# LB_BIT_i2_TOGGLESWITCH-v03_rev2.net
KiCad netlist of a schematic drawn in EAGLE
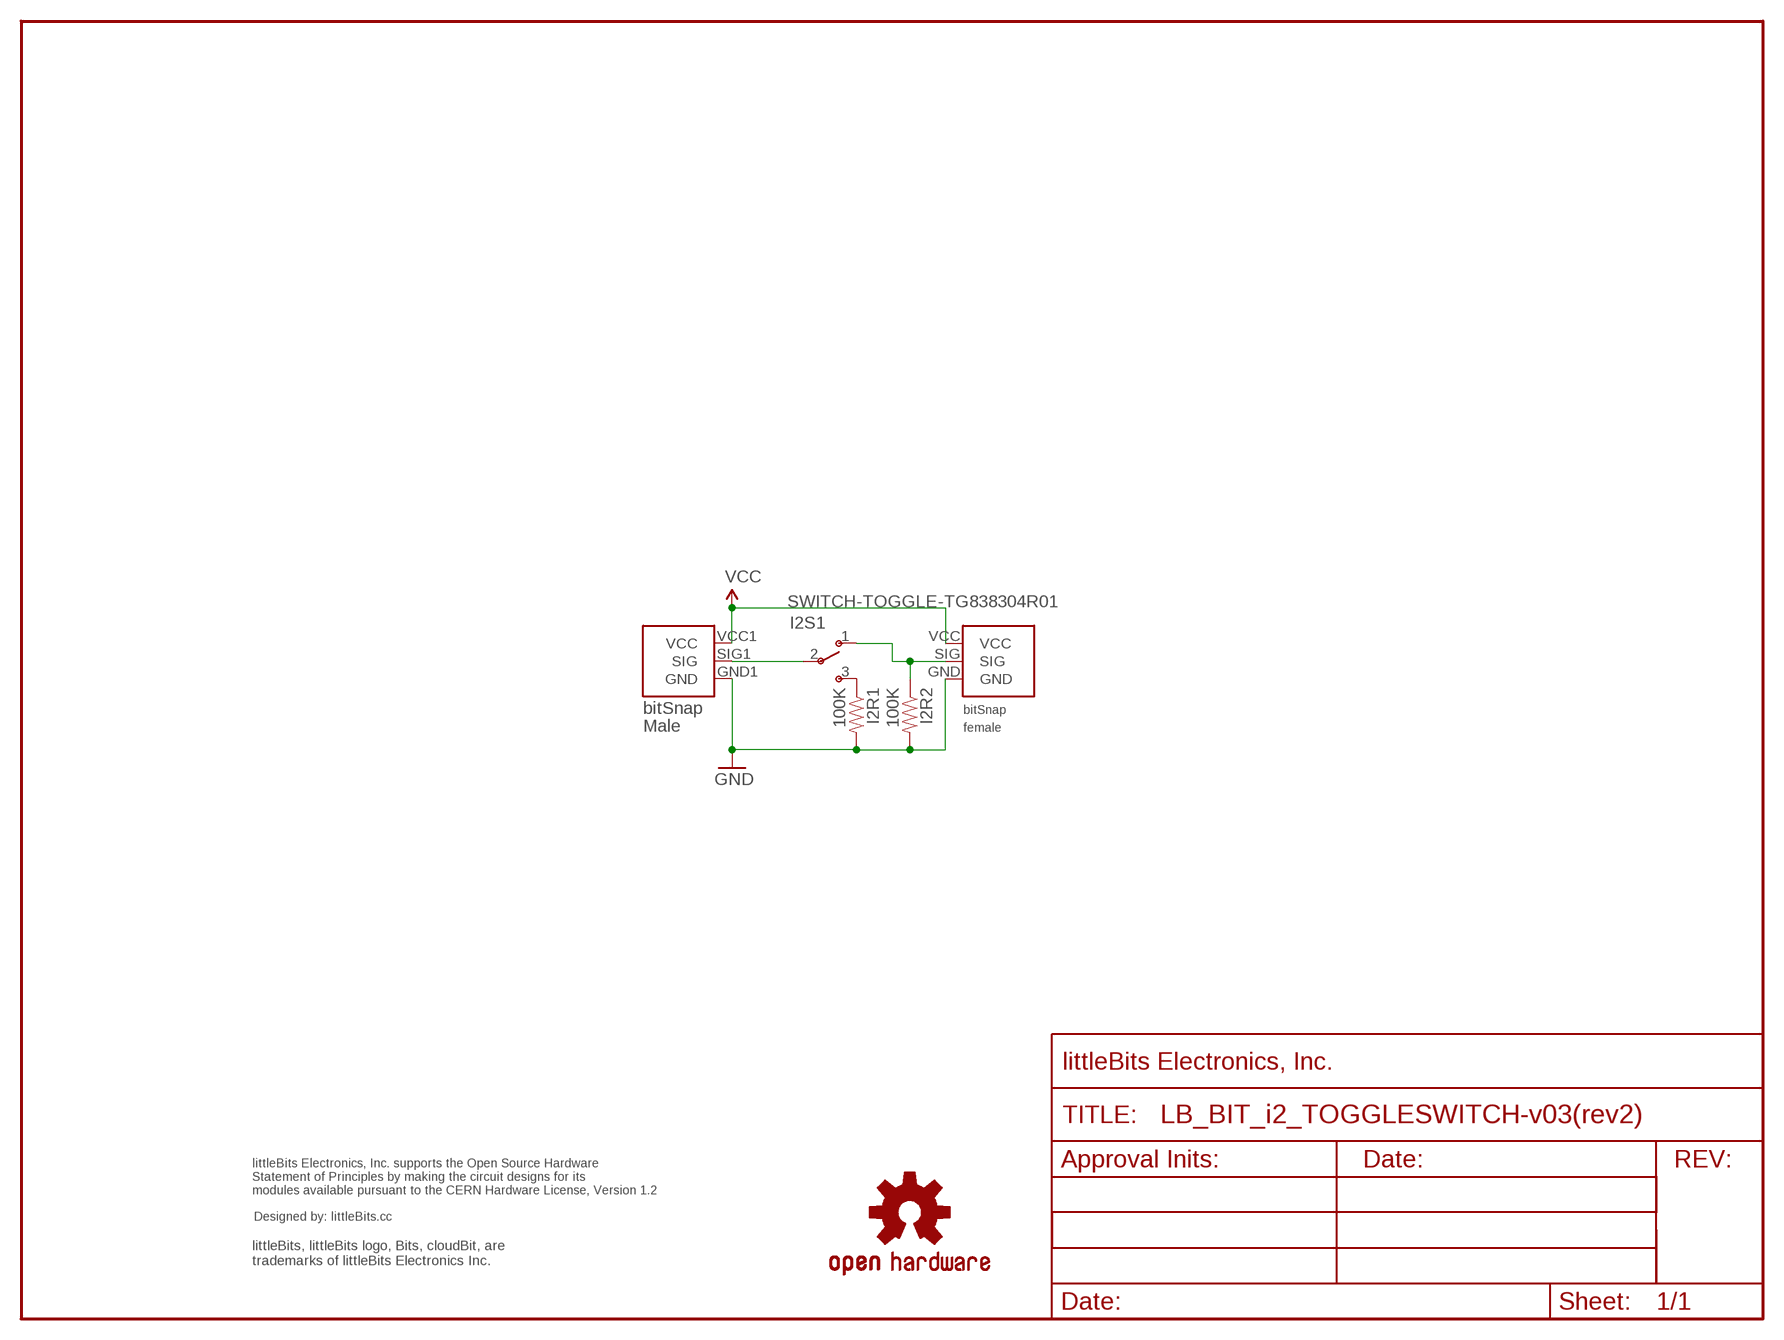
[diagram p0: schematic, sheet 1]

(export (version "E")
  (design (tool "Eeschema 10.0.6"))
  (components
    (comp (ref "FRAME1")
      (value "FRAME-LETTER-OHWOHW")
      (footprint "eagle-import:FABDWG01-OHW")
      (libsource (lib "eagle-import") (part "FRAME-LETTER-OHWOHW"))
    )
    (comp (ref "I2BSF1")
      (value "BITSNAP_V03_FEMALE")
      (footprint "eagle-import:BITSNAP_V03_FEMALE")
      (libsource (lib "eagle-import") (part "BITSNAP_V03_FEMALE"))
    )
    (comp (ref "I2BSM1")
      (value "BITSNAP_V03_MALE")
      (footprint "eagle-import:BITSNAP_V03_MALE")
      (libsource (lib "eagle-import") (part "BITSNAP_V03_MALE"))
    )
    (comp (ref "I2R1")
      (value "100K")
      (footprint "eagle-import:0603-RES")
      (libsource (lib "eagle-import") (part "RESISTOR0603-RES"))
    )
    (comp (ref "I2R2")
      (value "100K")
      (footprint "eagle-import:0603-RES")
      (libsource (lib "eagle-import") (part "RESISTOR0603-RES"))
    )
    (comp (ref "I2S1")
      (value "SWITCH-TOGGLE-TG838304R01")
      (footprint "eagle-import:SWITCH-TOGGLE-TG838304R01")
      (libsource (lib "eagle-import") (part "SWITCH-TOGGLE-TG838304R01"))
    )
    (comp (ref "U$2")
      (value "OSHWCREDIT")
      (footprint "eagle-import:OSHWCREDIT")
      (libsource (lib "eagle-import") (part "OSHWCREDIT"))
    )
    (comp (ref "U$7")
      (value "OSHW-LOGOL")
      (footprint "eagle-import:OSHW-LOGO-L")
      (libsource (lib "eagle-import") (part "OSHW-LOGOL"))
    )
  )
  (nets
    (net (code "1") (name "GND") (class "Default")
      (node (ref "I2BSF1") (pin "GND") (pinfunction "GND_GND") (pintype "bidirectional"))
      (node (ref "I2BSM1") (pin "GND1") (pinfunction "GND_GND1") (pintype "bidirectional"))
      (node (ref "I2R1") (pin "2") (pinfunction "2_2") (pintype "passive"))
      (node (ref "I2R2") (pin "2") (pinfunction "2_2") (pintype "passive"))
    )
    (net (code "2") (name "Net-(I2BSM1-SIG)") (class "Default")
      (node (ref "I2BSM1") (pin "SIG1") (pinfunction "SIG_SIG1") (pintype "bidirectional"))
      (node (ref "I2S1") (pin "2") (pinfunction "P_2") (pintype "passive"))
    )
    (net (code "3") (name "Net-(I2S1-O)") (class "Default")
      (node (ref "I2BSF1") (pin "SIG") (pinfunction "SIG_SIG") (pintype "bidirectional"))
      (node (ref "I2R2") (pin "1") (pinfunction "1_1") (pintype "passive"))
      (node (ref "I2S1") (pin "1") (pinfunction "O_1") (pintype "passive"))
    )
    (net (code "4") (name "Net-(I2S1-S)") (class "Default")
      (node (ref "I2R1") (pin "1") (pinfunction "1_1") (pintype "passive"))
      (node (ref "I2S1") (pin "3") (pinfunction "S_3") (pintype "passive"))
    )
    (net (code "5") (name "VCC") (class "Default")
      (node (ref "I2BSF1") (pin "VCC") (pinfunction "VCC_VCC") (pintype "bidirectional"))
      (node (ref "I2BSM1") (pin "VCC1") (pinfunction "VCC_VCC1") (pintype "bidirectional"))
    )
  )
)
